# Power.net
KiCad netlist of a schematic drawn in Altium Designer
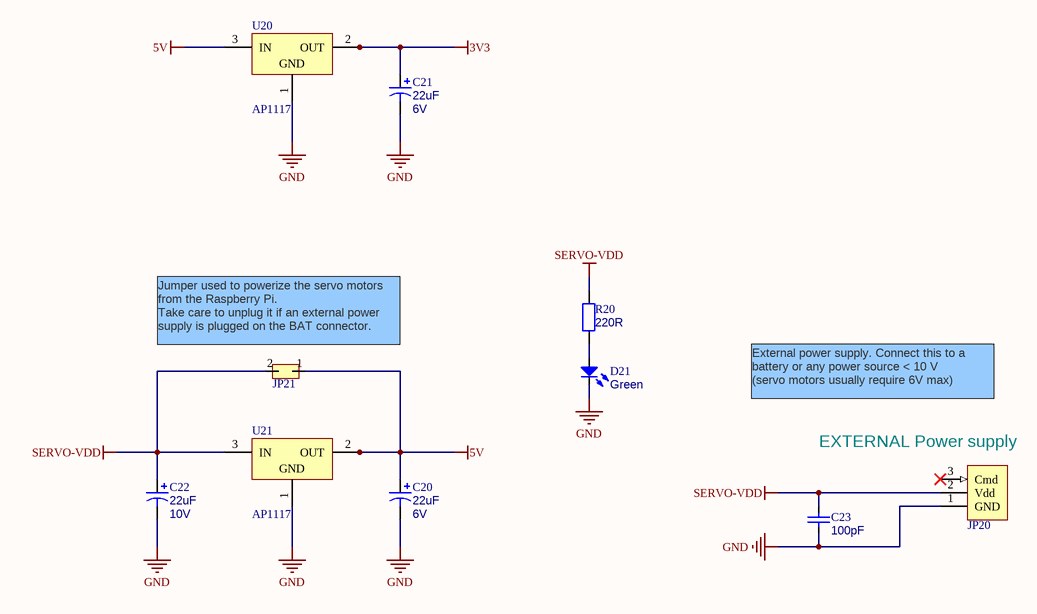
[diagram p0: Power.SchDoc]

(export (version "E")
  (design (tool "Eeschema 10.0.6"))
  (components
    (comp (ref "C20")
      (value "22uF")
      (footprint "TC3216-1206")
      (fields
        (field (name "VOLTAGE") "6V")
        (field (name "Comment") "Condensateur Polarise")
        (field (name "PUBLISHER") "Altium Limited")
      )
      (libsource (lib "Common") (part "Condensateur Polarise"))
    )
    (comp (ref "C21")
      (value "22uF")
      (footprint "TC3216-1206")
      (fields
        (field (name "VOLTAGE") "6V")
        (field (name "Comment") "Condensateur Polarise")
        (field (name "PUBLISHER") "Altium Limited")
      )
      (libsource (lib "Common") (part "Condensateur Polarise"))
    )
    (comp (ref "C22")
      (value "22uF")
      (footprint "TC3216-1206")
      (fields
        (field (name "VOLTAGE") "10V")
        (field (name "Comment") "Condensateur Polarise")
        (field (name "PUBLISHER") "Altium Limited")
      )
      (libsource (lib "Common") (part "Condensateur Polarise"))
    )
    (comp (ref "C23")
      (value "100pF")
      (footprint "CC1005-0402")
      (fields (field (name "Comment") "Condensateur"))
      (libsource (lib "Common") (part "Condensateur"))
    )
    (comp (ref "D21")
      (value "Led")
      (footprint "DIODE-0603")
      (fields (field (name "COLOR") "Green"))
      (libsource (lib "Common") (part "Led"))
    )
    (comp (ref "JP20")
      (value "SERVO Connector")
      (footprint "PinHead-3pts")
      (libsource (lib "OpenSCB") (part "SERVO-Connector"))
    )
    (comp (ref "JP21")
      (value "Jumper")
      (footprint "HDR1X2")
      (description "Header 2 pts")
      (libsource (lib "Connectors") (part "Jumper"))
    )
    (comp (ref "R20")
      (value "220R")
      (footprint "CR1005-0402")
      (fields (field (name "POWER") "0.5W") (field (name "Comment") "Resistance"))
      (libsource (lib "Common") (part "Resistance"))
    )
    (comp (ref "U20")
      (value "AP1117")
      (footprint "SOT-89")
      (description "AP1117 - 3V3 Voltage Regulator")
      (libsource (lib "OpenSCB") (part "AP1117"))
    )
    (comp (ref "U21")
      (value "AP1117")
      (footprint "SOT-89")
      (description "AP1117 - 3V3 Voltage Regulator")
      (libsource (lib "OpenSCB") (part "AP1117"))
    )
  )
  (nets
    (net (code "1") (name "3V3") (class "Default")
      (node (ref "C21") (pin "1") (pinfunction "1_1") (pintype "passive"))
      (node (ref "U20") (pin "0") (pinfunction "OUT_0") (pintype "power_in"))
      (node (ref "U20") (pin "2") (pinfunction "OUT_2") (pintype "power_in"))
    )
    (net (code "2") (name "5V") (class "Default")
      (node (ref "C20") (pin "1") (pinfunction "1_1") (pintype "passive"))
      (node (ref "JP21") (pin "1") (pintype "passive"))
      (node (ref "U20") (pin "3") (pinfunction "IN_3") (pintype "power_in"))
      (node (ref "U21") (pin "0") (pinfunction "OUT_0") (pintype "power_in"))
      (node (ref "U21") (pin "2") (pinfunction "OUT_2") (pintype "power_in"))
    )
    (net (code "3") (name "GND") (class "Default")
      (node (ref "C20") (pin "2") (pinfunction "2_2") (pintype "passive"))
      (node (ref "C21") (pin "2") (pinfunction "2_2") (pintype "passive"))
      (node (ref "C22") (pin "2") (pinfunction "2_2") (pintype "passive"))
      (node (ref "C23") (pin "1") (pinfunction "1_1") (pintype "passive"))
      (node (ref "D21") (pin "2") (pinfunction "K_2") (pintype "passive"))
      (node (ref "JP20") (pin "1") (pinfunction "GND_1") (pintype "power_in"))
      (node (ref "U20") (pin "1") (pinfunction "GND_1") (pintype "power_in"))
      (node (ref "U21") (pin "1") (pinfunction "GND_1") (pintype "power_in"))
    )
    (net (code "4") (name "Net-(D21-A)") (class "Default")
      (node (ref "D21") (pin "1") (pinfunction "A_1") (pintype "passive"))
      (node (ref "R20") (pin "1") (pinfunction "1_1") (pintype "passive"))
    )
    (net (code "5") (name "SERVO-VDD") (class "Default")
      (node (ref "C22") (pin "1") (pinfunction "1_1") (pintype "passive"))
      (node (ref "C23") (pin "2") (pinfunction "2_2") (pintype "passive"))
      (node (ref "JP20") (pin "2") (pinfunction "Vdd_2") (pintype "power_in"))
      (node (ref "JP21") (pin "2") (pintype "passive"))
      (node (ref "R20") (pin "2") (pinfunction "2_2") (pintype "passive"))
      (node (ref "U21") (pin "3") (pinfunction "IN_3") (pintype "power_in"))
    )
    (net (code "6") (name "unconnected-(JP20-Cmd-Pad3)") (class "Default")
      (node (ref "JP20") (pin "3") (pinfunction "Cmd_3") (pintype "input+no_connect"))
    )
  )
)
